# I2C.net
KiCad netlist of a schematic drawn in Altium Designer
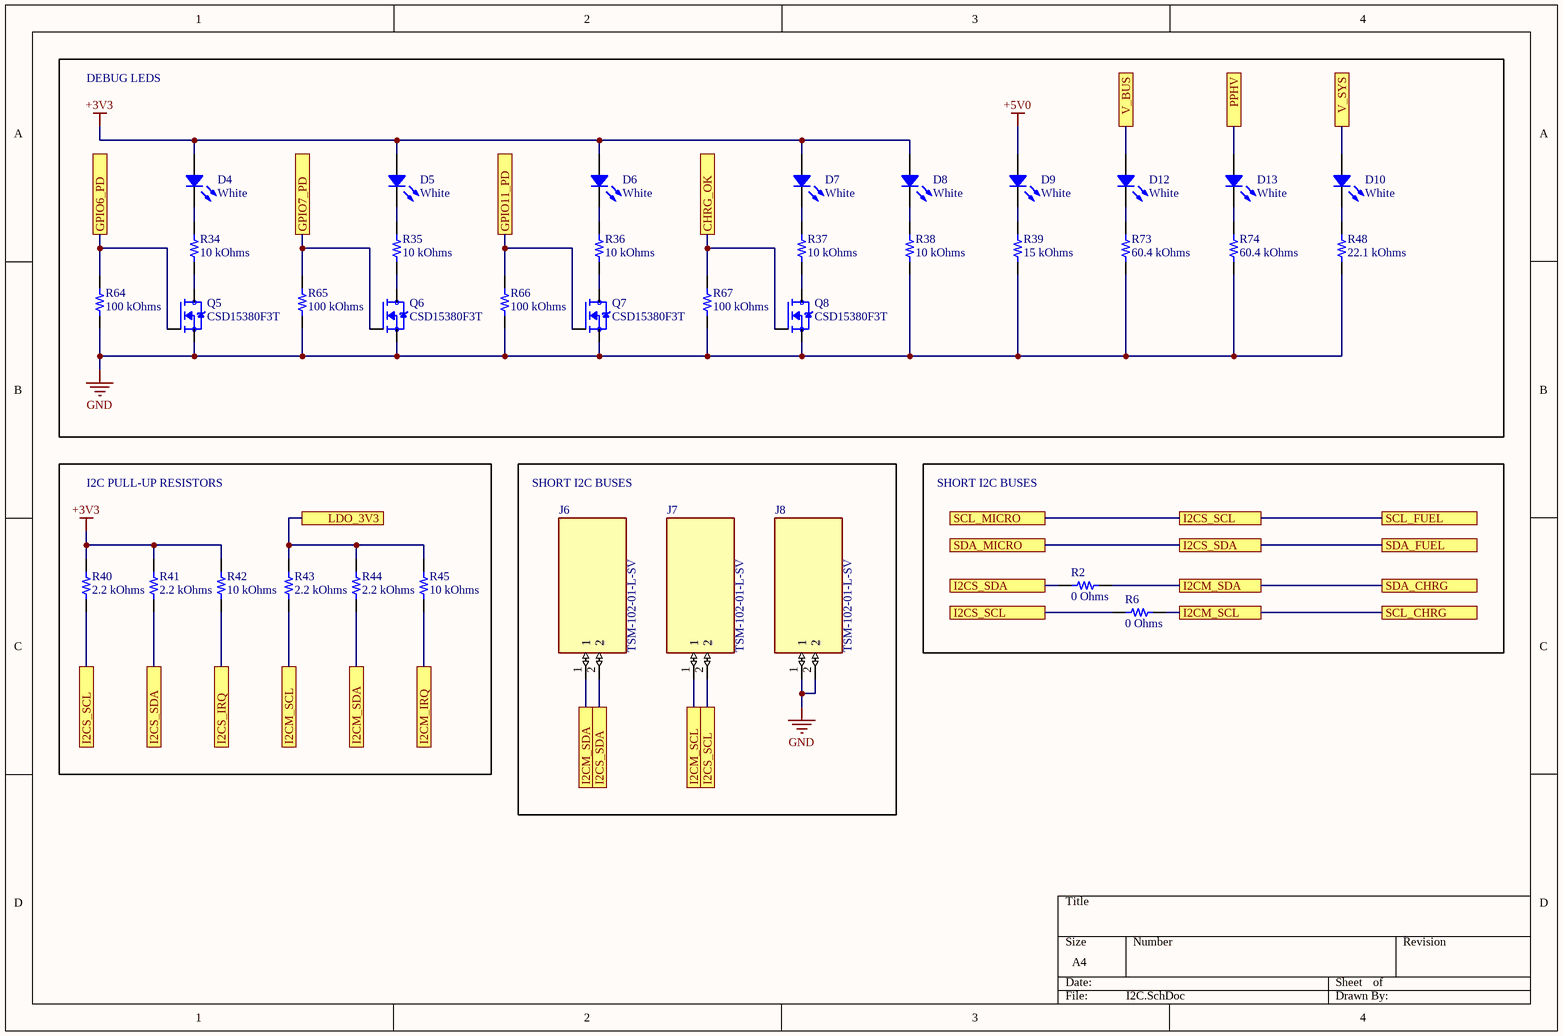
[diagram p0: I2C.SchDoc]

(export (version "E")
  (design (tool "Eeschema 10.0.6"))
  (components
    (comp (ref "D4")
      (value "White")
      (footprint "LED 0805_2012")
      (description "0805 LED WHITE, YELLOW DIFFUSED")
      (fields (field (name "PART NUMBER") "QBLP631-IW5") (field (name "MANUFACTURER") "QT Brightek (QTB)"))
      (libsource (lib "Celestial Altium Library - altium_library") (part "LED"))
    )
    (comp (ref "D5")
      (value "White")
      (footprint "LED 0805_2012")
      (description "0805 LED WHITE, YELLOW DIFFUSED")
      (fields (field (name "PART NUMBER") "QBLP631-IW5") (field (name "MANUFACTURER") "QT Brightek (QTB)"))
      (libsource (lib "Celestial Altium Library - altium_library") (part "LED"))
    )
    (comp (ref "D6")
      (value "White")
      (footprint "LED 0805_2012")
      (description "0805 LED WHITE, YELLOW DIFFUSED")
      (fields (field (name "PART NUMBER") "QBLP631-IW5") (field (name "MANUFACTURER") "QT Brightek (QTB)"))
      (libsource (lib "Celestial Altium Library - altium_library") (part "LED"))
    )
    (comp (ref "D7")
      (value "White")
      (footprint "LED 0805_2012")
      (description "0805 LED WHITE, YELLOW DIFFUSED")
      (fields (field (name "PART NUMBER") "QBLP631-IW5") (field (name "MANUFACTURER") "QT Brightek (QTB)"))
      (libsource (lib "Celestial Altium Library - altium_library") (part "LED"))
    )
    (comp (ref "D8")
      (value "White")
      (footprint "LED 0805_2012")
      (description "0805 LED WHITE, YELLOW DIFFUSED")
      (fields (field (name "PART NUMBER") "QBLP631-IW5") (field (name "MANUFACTURER") "QT Brightek (QTB)"))
      (libsource (lib "Celestial Altium Library - altium_library") (part "LED"))
    )
    (comp (ref "D9")
      (value "White")
      (footprint "LED 0805_2012")
      (description "0805 LED WHITE, YELLOW DIFFUSED")
      (fields (field (name "PART NUMBER") "QBLP631-IW5") (field (name "MANUFACTURER") "QT Brightek (QTB)"))
      (libsource (lib "Celestial Altium Library - altium_library") (part "LED"))
    )
    (comp (ref "D10")
      (value "White")
      (footprint "LED 0805_2012")
      (description "0805 LED WHITE, YELLOW DIFFUSED")
      (fields (field (name "PART NUMBER") "QBLP631-IW5") (field (name "MANUFACTURER") "QT Brightek (QTB)"))
      (libsource (lib "Celestial Altium Library - altium_library") (part "LED"))
    )
    (comp (ref "D12")
      (value "White")
      (footprint "LED 0805_2012")
      (description "0805 LED WHITE, YELLOW DIFFUSED")
      (fields (field (name "PART NUMBER") "QBLP631-IW5") (field (name "MANUFACTURER") "QT Brightek (QTB)"))
      (libsource (lib "Celestial Altium Library - altium_library") (part "LED"))
    )
    (comp (ref "D13")
      (value "White")
      (footprint "LED 0805_2012")
      (description "0805 LED WHITE, YELLOW DIFFUSED")
      (fields (field (name "PART NUMBER") "QBLP631-IW5") (field (name "MANUFACTURER") "QT Brightek (QTB)"))
      (libsource (lib "Celestial Altium Library - altium_library") (part "LED"))
    )
    (comp (ref "J6")
      (value "TSM-102-01-L-SV")
      (footprint "TSM-102-01-L-SV-P-TR:TSM-102-01-L-SV")
      (fields (field (name "MF") "{'manufacturer': u'Samtec Inc.'}"))
      (libsource (lib "*") (part "TSM-102-01-L-SV"))
    )
    (comp (ref "J7")
      (value "TSM-102-01-L-SV")
      (footprint "TSM-102-01-L-SV-P-TR:TSM-102-01-L-SV")
      (fields (field (name "MF") "{'manufacturer': u'Samtec Inc.'}"))
      (libsource (lib "*") (part "TSM-102-01-L-SV"))
    )
    (comp (ref "J8")
      (value "TSM-102-01-L-SV")
      (footprint "TSM-102-01-L-SV-P-TR:TSM-102-01-L-SV")
      (fields (field (name "MF") "{'manufacturer': u'Samtec Inc.'}"))
      (libsource (lib "*") (part "TSM-102-01-L-SV"))
    )
    (comp (ref "Q5")
      (value "CSD15380F3T")
      (footprint "CSD15380F3T:TRXDFN69X60X35-3N")
      (description "20-V N-Channel FemtoFET MOSFET 3-PICOSTAR -55 to 150")
      (fields (field (name "MF") "{'manufacturer': u'Texas Instruments'}"))
      (libsource (lib "*") (part "CSD15380F3T"))
    )
    (comp (ref "Q6")
      (value "CSD15380F3T")
      (footprint "CSD15380F3T:TRXDFN69X60X35-3N")
      (description "20-V N-Channel FemtoFET MOSFET 3-PICOSTAR -55 to 150")
      (fields (field (name "MF") "{'manufacturer': u'Texas Instruments'}"))
      (libsource (lib "*") (part "CSD15380F3T"))
    )
    (comp (ref "Q7")
      (value "CSD15380F3T")
      (footprint "CSD15380F3T:TRXDFN69X60X35-3N")
      (description "20-V N-Channel FemtoFET MOSFET 3-PICOSTAR -55 to 150")
      (fields (field (name "MF") "{'manufacturer': u'Texas Instruments'}"))
      (libsource (lib "*") (part "CSD15380F3T"))
    )
    (comp (ref "Q8")
      (value "CSD15380F3T")
      (footprint "CSD15380F3T:TRXDFN69X60X35-3N")
      (description "20-V N-Channel FemtoFET MOSFET 3-PICOSTAR -55 to 150")
      (fields (field (name "MF") "{'manufacturer': u'Texas Instruments'}"))
      (libsource (lib "*") (part "CSD15380F3T"))
    )
    (comp (ref "R2")
      (value "0 Ohms")
      (footprint "RES 0402_1005")
      (description "RES SMD 0 OHM JUMPER 1/5W 0402")
      (fields (field (name "PART NUMBER") "CRCW04020000Z0EDHP") (field (name "MANUFACTURER") "Vishay Dale"))
      (libsource (lib "Celestial Altium Library - altium_library") (part "Resistor"))
    )
    (comp (ref "R6")
      (value "0 Ohms")
      (footprint "RES 0402_1005")
      (description "RES SMD 0 OHM JUMPER 1/5W 0402")
      (fields (field (name "PART NUMBER") "CRCW04020000Z0EDHP") (field (name "MANUFACTURER") "Vishay Dale"))
      (libsource (lib "Celestial Altium Library - altium_library") (part "Resistor"))
    )
    (comp (ref "R34")
      (value "10 kOhms")
      (footprint "RES 0603_1608")
      (description "RES 10K OHM 5% 0.01W 0603")
      (fields (field (name "PART NUMBER") "CR0603-JW-103EAS") (field (name "MANUFACTURER") "Bourns Inc."))
      (libsource (lib "Celestial Altium Library - altium_library") (part "Resistor"))
    )
    (comp (ref "R35")
      (value "10 kOhms")
      (footprint "RES 0603_1608")
      (description "RES 10K OHM 5% 0.01W 0603")
      (fields (field (name "PART NUMBER") "CR0603-JW-103EAS") (field (name "MANUFACTURER") "Bourns Inc."))
      (libsource (lib "Celestial Altium Library - altium_library") (part "Resistor"))
    )
    (comp (ref "R36")
      (value "10 kOhms")
      (footprint "RES 0603_1608")
      (description "RES 10K OHM 5% 0.01W 0603")
      (fields (field (name "PART NUMBER") "CR0603-JW-103EAS") (field (name "MANUFACTURER") "Bourns Inc."))
      (libsource (lib "Celestial Altium Library - altium_library") (part "Resistor"))
    )
    (comp (ref "R37")
      (value "10 kOhms")
      (footprint "RES 0603_1608")
      (description "RES 10K OHM 5% 0.01W 0603")
      (fields (field (name "PART NUMBER") "CR0603-JW-103EAS") (field (name "MANUFACTURER") "Bourns Inc."))
      (libsource (lib "Celestial Altium Library - altium_library") (part "Resistor"))
    )
    (comp (ref "R38")
      (value "10 kOhms")
      (footprint "RES 0603_1608")
      (description "RES 10K OHM 5% 0.01W 0603")
      (fields (field (name "PART NUMBER") "CR0603-JW-103EAS") (field (name "MANUFACTURER") "Bourns Inc."))
      (libsource (lib "Celestial Altium Library - altium_library") (part "Resistor"))
    )
    (comp (ref "R39")
      (value "15 kOhms")
      (footprint "RES 0402_1005")
      (description "RES 15K OHM 1% 1/16W 0402")
      (fields (field (name "PART NUMBER") "RC0402FR-1315KL") (field (name "MANUFACTURER") "Yageo"))
      (libsource (lib "Celestial Altium Library - altium_library") (part "Resistor"))
    )
    (comp (ref "R40")
      (value "2.2 kOhms")
      (footprint "RES 0402_1005")
      (description "RES 2.2K OHM 1% 1/16W 0402")
      (fields (field (name "PART NUMBER") "RC0402FR-132K2L") (field (name "MANUFACTURER") "Yageo"))
      (libsource (lib "Celestial Altium Library - altium_library") (part "Resistor"))
    )
    (comp (ref "R41")
      (value "2.2 kOhms")
      (footprint "RES 0402_1005")
      (description "RES 2.2K OHM 1% 1/16W 0402")
      (fields (field (name "PART NUMBER") "RC0402FR-132K2L") (field (name "MANUFACTURER") "Yageo"))
      (libsource (lib "Celestial Altium Library - altium_library") (part "Resistor"))
    )
    (comp (ref "R42")
      (value "10 kOhms")
      (footprint "RES 0402_1005")
      (description "RES 10K OHM 5% 1/16W 0402")
      (fields (field (name "PART NUMBER") "RC0402JR-1310KL") (field (name "MANUFACTURER") "Yageo"))
      (libsource (lib "Celestial Altium Library - altium_library") (part "Resistor"))
    )
    (comp (ref "R43")
      (value "2.2 kOhms")
      (footprint "RES 0402_1005")
      (description "RES 2.2K OHM 1% 1/16W 0402")
      (fields (field (name "PART NUMBER") "RC0402FR-132K2L") (field (name "MANUFACTURER") "Yageo"))
      (libsource (lib "Celestial Altium Library - altium_library") (part "Resistor"))
    )
    (comp (ref "R44")
      (value "2.2 kOhms")
      (footprint "RES 0402_1005")
      (description "RES 2.2K OHM 1% 1/16W 0402")
      (fields (field (name "PART NUMBER") "RC0402FR-132K2L") (field (name "MANUFACTURER") "Yageo"))
      (libsource (lib "Celestial Altium Library - altium_library") (part "Resistor"))
    )
    (comp (ref "R45")
      (value "10 kOhms")
      (footprint "RES 0402_1005")
      (description "RES 10K OHM 5% 1/16W 0402")
      (fields (field (name "PART NUMBER") "RC0402JR-1310KL") (field (name "MANUFACTURER") "Yageo"))
      (libsource (lib "Celestial Altium Library - altium_library") (part "Resistor"))
    )
    (comp (ref "R48")
      (value "22.1 kOhms")
      (footprint "RES 0603_1608")
      (description "RES 22.1K OHM 1% 1/10W 0603")
      (fields
        (field (name "PART NUMBER") "RMCF0603FT22K1")
        (field (name "MANUFACTURER") "Stackpole Electronics Inc")
      )
      (libsource (lib "Celestial Altium Library - altium_library") (part "Resistor"))
    )
    (comp (ref "R64")
      (value "100 kOhms")
      (footprint "RES 0402_1005")
      (description "RES SMD 100K OHM 1% 1/16W 0402")
      (fields (field (name "PART NUMBER") "RT0402FRE07100KL") (field (name "MANUFACTURER") "Yageo"))
      (libsource (lib "Celestial Altium Library - altium_library") (part "Resistor"))
    )
    (comp (ref "R65")
      (value "100 kOhms")
      (footprint "RES 0402_1005")
      (description "RES SMD 100K OHM 1% 1/16W 0402")
      (fields (field (name "PART NUMBER") "RT0402FRE07100KL") (field (name "MANUFACTURER") "Yageo"))
      (libsource (lib "Celestial Altium Library - altium_library") (part "Resistor"))
    )
    (comp (ref "R66")
      (value "100 kOhms")
      (footprint "RES 0402_1005")
      (description "RES SMD 100K OHM 1% 1/16W 0402")
      (fields (field (name "PART NUMBER") "RT0402FRE07100KL") (field (name "MANUFACTURER") "Yageo"))
      (libsource (lib "Celestial Altium Library - altium_library") (part "Resistor"))
    )
    (comp (ref "R67")
      (value "100 kOhms")
      (footprint "RES 0402_1005")
      (description "RES SMD 100K OHM 1% 1/16W 0402")
      (fields (field (name "PART NUMBER") "RT0402FRE07100KL") (field (name "MANUFACTURER") "Yageo"))
      (libsource (lib "Celestial Altium Library - altium_library") (part "Resistor"))
    )
    (comp (ref "R73")
      (value "60.4 kOhms")
      (footprint "RES 0603_1608")
      (description "RES SMD 60.4K OHM 1% 1/10W 0603")
      (fields (field (name "PART NUMBER") "CRCW060360K4FKEA") (field (name "MANUFACTURER") "Vishay Dale"))
      (libsource (lib "Celestial Altium Library - altium_library") (part "Resistor"))
    )
    (comp (ref "R74")
      (value "60.4 kOhms")
      (footprint "RES 0603_1608")
      (description "RES SMD 60.4K OHM 1% 1/10W 0603")
      (fields (field (name "PART NUMBER") "CRCW060360K4FKEA") (field (name "MANUFACTURER") "Vishay Dale"))
      (libsource (lib "Celestial Altium Library - altium_library") (part "Resistor"))
    )
  )
  (nets
    (net (code "1") (name "+3V3") (class "Default")
      (node (ref "D4") (pin "1") (pinfunction "1_1") (pintype "passive"))
      (node (ref "D5") (pin "1") (pinfunction "1_1") (pintype "passive"))
      (node (ref "D6") (pin "1") (pinfunction "1_1") (pintype "passive"))
      (node (ref "D7") (pin "1") (pinfunction "1_1") (pintype "passive"))
      (node (ref "D8") (pin "1") (pinfunction "1_1") (pintype "passive"))
      (node (ref "R40") (pin "2") (pinfunction "2_2") (pintype "passive"))
      (node (ref "R41") (pin "2") (pinfunction "2_2") (pintype "passive"))
      (node (ref "R42") (pin "2") (pinfunction "2_2") (pintype "passive"))
    )
    (net (code "2") (name "+5V0") (class "Default")
      (node (ref "D9") (pin "1") (pinfunction "1_1") (pintype "passive"))
    )
    (net (code "3") (name "/CHRG_OK") (class "Default")
      (node (ref "Q8") (pin "1") (pinfunction "G_1") (pintype "passive"))
      (node (ref "R67") (pin "2") (pinfunction "2_2") (pintype "passive"))
    )
    (net (code "4") (name "/GPIO6_PD") (class "Default")
      (node (ref "Q5") (pin "1") (pinfunction "G_1") (pintype "passive"))
      (node (ref "R64") (pin "2") (pinfunction "2_2") (pintype "passive"))
    )
    (net (code "5") (name "/GPIO7_PD") (class "Default")
      (node (ref "Q6") (pin "1") (pinfunction "G_1") (pintype "passive"))
      (node (ref "R65") (pin "2") (pinfunction "2_2") (pintype "passive"))
    )
    (net (code "6") (name "/GPIO11_PD") (class "Default")
      (node (ref "Q7") (pin "1") (pinfunction "G_1") (pintype "passive"))
      (node (ref "R66") (pin "2") (pinfunction "2_2") (pintype "passive"))
    )
    (net (code "7") (name "/I2CM_IRQ") (class "Default")
      (node (ref "R45") (pin "1") (pinfunction "1_1") (pintype "passive"))
    )
    (net (code "8") (name "/I2CM_SCL") (class "Default")
      (node (ref "J7") (pin "1") (pinfunction "1_1") (pintype "bidirectional"))
      (node (ref "R43") (pin "1") (pinfunction "1_1") (pintype "passive"))
      (node (ref "R6") (pin "2") (pinfunction "2_2") (pintype "passive"))
    )
    (net (code "9") (name "/I2CM_SDA") (class "Default")
      (node (ref "J6") (pin "1") (pinfunction "1_1") (pintype "bidirectional"))
      (node (ref "R2") (pin "2") (pinfunction "2_2") (pintype "passive"))
      (node (ref "R44") (pin "1") (pinfunction "1_1") (pintype "passive"))
    )
    (net (code "10") (name "/I2CS_IRQ") (class "Default")
      (node (ref "R42") (pin "1") (pinfunction "1_1") (pintype "passive"))
    )
    (net (code "11") (name "/I2CS_SCL") (class "Default")
      (node (ref "J7") (pin "2") (pinfunction "2_2") (pintype "bidirectional"))
      (node (ref "R40") (pin "1") (pinfunction "1_1") (pintype "passive"))
      (node (ref "R6") (pin "1") (pinfunction "1_1") (pintype "passive"))
    )
    (net (code "12") (name "/I2CS_SDA") (class "Default")
      (node (ref "J6") (pin "2") (pinfunction "2_2") (pintype "bidirectional"))
      (node (ref "R2") (pin "1") (pinfunction "1_1") (pintype "passive"))
      (node (ref "R41") (pin "1") (pinfunction "1_1") (pintype "passive"))
    )
    (net (code "13") (name "/LDO_3V3") (class "Default")
      (node (ref "R43") (pin "2") (pinfunction "2_2") (pintype "passive"))
      (node (ref "R44") (pin "2") (pinfunction "2_2") (pintype "passive"))
      (node (ref "R45") (pin "2") (pinfunction "2_2") (pintype "passive"))
    )
    (net (code "14") (name "/PPHV") (class "Default")
      (node (ref "D13") (pin "1") (pinfunction "1_1") (pintype "passive"))
    )
    (net (code "15") (name "/V_BUS") (class "Default")
      (node (ref "D12") (pin "1") (pinfunction "1_1") (pintype "passive"))
    )
    (net (code "16") (name "/V_SYS") (class "Default")
      (node (ref "D10") (pin "1") (pinfunction "1_1") (pintype "passive"))
    )
    (net (code "17") (name "GND") (class "Default")
      (node (ref "J8") (pin "1") (pinfunction "1_1") (pintype "bidirectional"))
      (node (ref "J8") (pin "2") (pinfunction "2_2") (pintype "bidirectional"))
      (node (ref "Q5") (pin "2") (pinfunction "S_2") (pintype "passive"))
      (node (ref "Q6") (pin "2") (pinfunction "S_2") (pintype "passive"))
      (node (ref "Q7") (pin "2") (pinfunction "S_2") (pintype "passive"))
      (node (ref "Q8") (pin "2") (pinfunction "S_2") (pintype "passive"))
      (node (ref "R38") (pin "1") (pinfunction "1_1") (pintype "passive"))
      (node (ref "R39") (pin "1") (pinfunction "1_1") (pintype "passive"))
      (node (ref "R48") (pin "1") (pinfunction "1_1") (pintype "passive"))
      (node (ref "R64") (pin "1") (pinfunction "1_1") (pintype "passive"))
      (node (ref "R65") (pin "1") (pinfunction "1_1") (pintype "passive"))
      (node (ref "R66") (pin "1") (pinfunction "1_1") (pintype "passive"))
      (node (ref "R67") (pin "1") (pinfunction "1_1") (pintype "passive"))
      (node (ref "R73") (pin "1") (pinfunction "1_1") (pintype "passive"))
      (node (ref "R74") (pin "1") (pinfunction "1_1") (pintype "passive"))
    )
    (net (code "18") (name "Net-(D4-Pad2)") (class "Default")
      (node (ref "D4") (pin "2") (pinfunction "2_2") (pintype "passive"))
      (node (ref "R34") (pin "2") (pinfunction "2_2") (pintype "passive"))
    )
    (net (code "19") (name "Net-(D5-Pad2)") (class "Default")
      (node (ref "D5") (pin "2") (pinfunction "2_2") (pintype "passive"))
      (node (ref "R35") (pin "2") (pinfunction "2_2") (pintype "passive"))
    )
    (net (code "20") (name "Net-(D6-Pad2)") (class "Default")
      (node (ref "D6") (pin "2") (pinfunction "2_2") (pintype "passive"))
      (node (ref "R36") (pin "2") (pinfunction "2_2") (pintype "passive"))
    )
    (net (code "21") (name "Net-(D7-Pad2)") (class "Default")
      (node (ref "D7") (pin "2") (pinfunction "2_2") (pintype "passive"))
      (node (ref "R37") (pin "2") (pinfunction "2_2") (pintype "passive"))
    )
    (net (code "22") (name "Net-(D8-Pad2)") (class "Default")
      (node (ref "D8") (pin "2") (pinfunction "2_2") (pintype "passive"))
      (node (ref "R38") (pin "2") (pinfunction "2_2") (pintype "passive"))
    )
    (net (code "23") (name "Net-(D9-Pad2)") (class "Default")
      (node (ref "D9") (pin "2") (pinfunction "2_2") (pintype "passive"))
      (node (ref "R39") (pin "2") (pinfunction "2_2") (pintype "passive"))
    )
    (net (code "24") (name "Net-(D10-Pad2)") (class "Default")
      (node (ref "D10") (pin "2") (pinfunction "2_2") (pintype "passive"))
      (node (ref "R48") (pin "2") (pinfunction "2_2") (pintype "passive"))
    )
    (net (code "25") (name "Net-(D12-Pad2)") (class "Default")
      (node (ref "D12") (pin "2") (pinfunction "2_2") (pintype "passive"))
      (node (ref "R73") (pin "2") (pinfunction "2_2") (pintype "passive"))
    )
    (net (code "26") (name "Net-(D13-Pad2)") (class "Default")
      (node (ref "D13") (pin "2") (pinfunction "2_2") (pintype "passive"))
      (node (ref "R74") (pin "2") (pinfunction "2_2") (pintype "passive"))
    )
    (net (code "27") (name "Net-(Q5-D)") (class "Default")
      (node (ref "Q5") (pin "3") (pinfunction "D_3") (pintype "passive"))
      (node (ref "R34") (pin "1") (pinfunction "1_1") (pintype "passive"))
    )
    (net (code "28") (name "Net-(Q6-D)") (class "Default")
      (node (ref "Q6") (pin "3") (pinfunction "D_3") (pintype "passive"))
      (node (ref "R35") (pin "1") (pinfunction "1_1") (pintype "passive"))
    )
    (net (code "29") (name "Net-(Q7-D)") (class "Default")
      (node (ref "Q7") (pin "3") (pinfunction "D_3") (pintype "passive"))
      (node (ref "R36") (pin "1") (pinfunction "1_1") (pintype "passive"))
    )
    (net (code "30") (name "Net-(Q8-D)") (class "Default")
      (node (ref "Q8") (pin "3") (pinfunction "D_3") (pintype "passive"))
      (node (ref "R37") (pin "1") (pinfunction "1_1") (pintype "passive"))
    )
  )
)
